# eilzugwagen.net
KiCad netlist of a schematic drawn in EAGLE
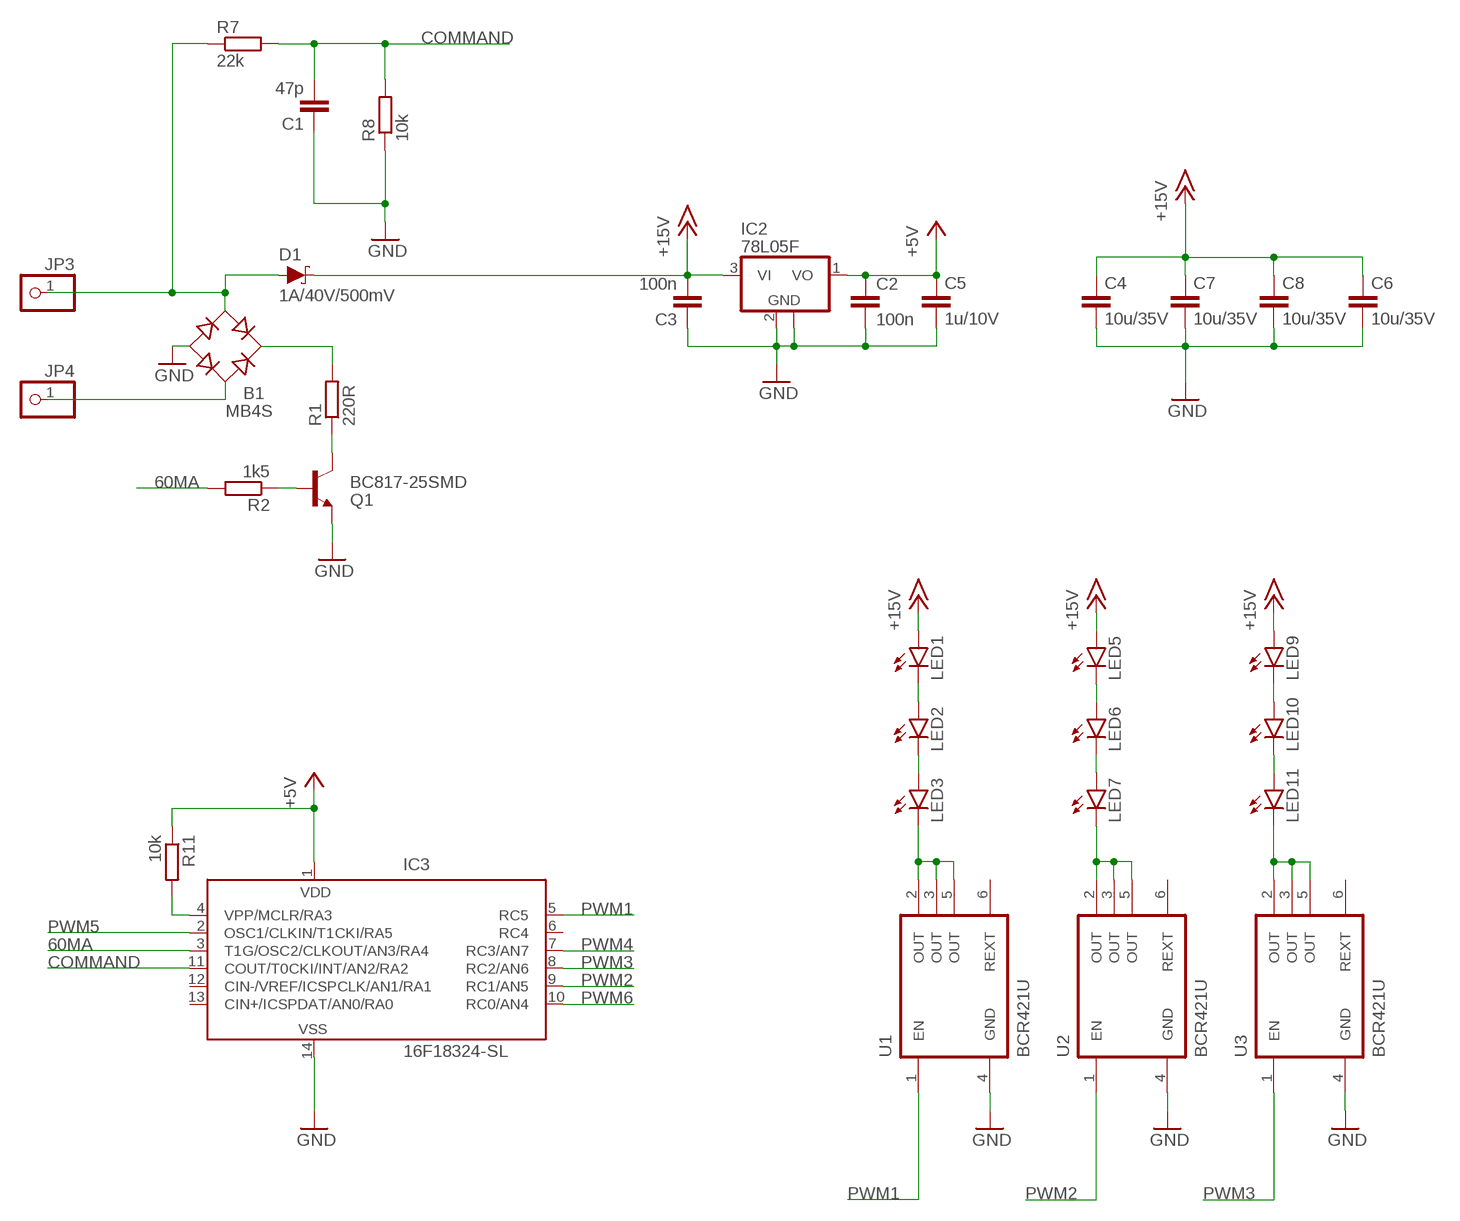
[diagram p0: schematic, sheet 1]

(export (version "E")
  (design (tool "Eeschema 10.0.6"))
  (components
    (comp (ref "B1")
      (value "MB4S")
      (footprint "eagle-import:SOIC-4")
      (libsource (lib "eagle-import") (part "MBS4"))
    )
    (comp (ref "C1")
      (value "47p")
      (footprint "eagle-import:C0805")
      (libsource (lib "eagle-import") (part "C-EUC0805"))
    )
    (comp (ref "C2")
      (value "100n")
      (footprint "eagle-import:C3216")
      (libsource (lib "eagle-import") (part "C-EUC3216"))
    )
    (comp (ref "C3")
      (value "100n")
      (footprint "eagle-import:C3216")
      (libsource (lib "eagle-import") (part "C-EUC3216"))
    )
    (comp (ref "C4")
      (value "10u/35V")
      (footprint "eagle-import:C3216")
      (libsource (lib "eagle-import") (part "C-EUC3216"))
    )
    (comp (ref "C5")
      (value "1u/10V")
      (footprint "eagle-import:C3216")
      (libsource (lib "eagle-import") (part "C-EUC3216"))
    )
    (comp (ref "C6")
      (value "10u/35V")
      (footprint "eagle-import:C3216")
      (libsource (lib "eagle-import") (part "C-EUC3216"))
    )
    (comp (ref "C7")
      (value "10u/35V")
      (footprint "eagle-import:C3216")
      (libsource (lib "eagle-import") (part "C-EUC3216"))
    )
    (comp (ref "C8")
      (value "10u/35V")
      (footprint "eagle-import:C3216")
      (libsource (lib "eagle-import") (part "C-EUC3216"))
    )
    (comp (ref "D1")
      (value "1A/40V/500mV")
      (footprint "eagle-import:SMA-DIODE")
      (libsource (lib "eagle-import") (part "DIODE-SCHOTTKY-SS14"))
    )
    (comp (ref "IC2")
      (value "78L05F")
      (footprint "eagle-import:SOT89")
      (libsource (lib "eagle-import") (part "78LF05"))
    )
    (comp (ref "IC3")
      (value "16F18324-SL")
      (footprint "eagle-import:SO-14")
      (fields (field (name "MF") "MICROCHIP") (field (name "MPN") "PIC16F676-I/SL"))
      (libsource (lib "eagle-import") (part "PIC16F676SL"))
    )
    (comp (ref "JP3")
      (value "PINHD-1X1")
      (footprint "eagle-import:1X01")
      (libsource (lib "eagle-import") (part "PINHD-1X1"))
    )
    (comp (ref "JP4")
      (value "PINHD-1X1")
      (footprint "eagle-import:1X01")
      (libsource (lib "eagle-import") (part "PINHD-1X1"))
    )
    (comp (ref "LED1")
      (value "LEDKA-3528ASYC")
      (footprint "eagle-import:KA-3528ASYC")
      (libsource (lib "eagle-import") (part "LEDKA-3528ASYC"))
    )
    (comp (ref "LED2")
      (value "LEDKA-3528ASYC")
      (footprint "eagle-import:KA-3528ASYC")
      (libsource (lib "eagle-import") (part "LEDKA-3528ASYC"))
    )
    (comp (ref "LED3")
      (value "LEDKA-3528ASYC")
      (footprint "eagle-import:KA-3528ASYC")
      (libsource (lib "eagle-import") (part "LEDKA-3528ASYC"))
    )
    (comp (ref "LED5")
      (value "LEDKA-3528ASYC")
      (footprint "eagle-import:KA-3528ASYC")
      (libsource (lib "eagle-import") (part "LEDKA-3528ASYC"))
    )
    (comp (ref "LED6")
      (value "LEDKA-3528ASYC")
      (footprint "eagle-import:KA-3528ASYC")
      (libsource (lib "eagle-import") (part "LEDKA-3528ASYC"))
    )
    (comp (ref "LED7")
      (value "LEDKA-3528ASYC")
      (footprint "eagle-import:KA-3528ASYC")
      (libsource (lib "eagle-import") (part "LEDKA-3528ASYC"))
    )
    (comp (ref "LED9")
      (value "LEDKA-3528ASYC")
      (footprint "eagle-import:KA-3528ASYC")
      (libsource (lib "eagle-import") (part "LEDKA-3528ASYC"))
    )
    (comp (ref "LED10")
      (value "LEDKA-3528ASYC")
      (footprint "eagle-import:KA-3528ASYC")
      (libsource (lib "eagle-import") (part "LEDKA-3528ASYC"))
    )
    (comp (ref "LED11")
      (value "LEDKA-3528ASYC")
      (footprint "eagle-import:KA-3528ASYC")
      (libsource (lib "eagle-import") (part "LEDKA-3528ASYC"))
    )
    (comp (ref "Q1")
      (value "BC817-25SMD")
      (footprint "eagle-import:SOT23-BEC")
      (libsource (lib "eagle-import") (part "BC817SMD-25"))
    )
    (comp (ref "R1")
      (value "220R")
      (footprint "eagle-import:R1206")
      (libsource (lib "eagle-import") (part "R-EU_R1206"))
    )
    (comp (ref "R2")
      (value "1k5")
      (footprint "eagle-import:R1206")
      (libsource (lib "eagle-import") (part "R-EU_R1206"))
    )
    (comp (ref "R7")
      (value "22k")
      (footprint "eagle-import:R1206")
      (libsource (lib "eagle-import") (part "R-EU_R1206"))
    )
    (comp (ref "R8")
      (value "10k")
      (footprint "eagle-import:R1206")
      (libsource (lib "eagle-import") (part "R-EU_R1206"))
    )
    (comp (ref "R11")
      (value "10k")
      (footprint "eagle-import:R1206")
      (libsource (lib "eagle-import") (part "R-EU_R1206"))
    )
    (comp (ref "U1")
      (value "BCR421U")
      (footprint "eagle-import:SC74-6")
      (fields (field (name "MF") "Infineon"))
      (libsource (lib "eagle-import") (part "BCR421U"))
    )
    (comp (ref "U2")
      (value "BCR421U")
      (footprint "eagle-import:SC74-6")
      (fields (field (name "MF") "Infineon"))
      (libsource (lib "eagle-import") (part "BCR421U"))
    )
    (comp (ref "U3")
      (value "BCR421U")
      (footprint "eagle-import:SC74-6")
      (fields (field (name "MF") "Infineon"))
      (libsource (lib "eagle-import") (part "BCR421U"))
    )
  )
  (nets
    (net (code "1") (name "+5V") (class "Default")
      (node (ref "C2") (pin "1") (pinfunction "1_1") (pintype "passive"))
      (node (ref "C5") (pin "1") (pinfunction "1_1") (pintype "passive"))
      (node (ref "IC2") (pin "1") (pinfunction "VO_1") (pintype "passive"))
      (node (ref "IC3") (pin "1") (pinfunction "VDD_1") (pintype "power_in"))
      (node (ref "R11") (pin "1") (pinfunction "1_1") (pintype "passive"))
    )
    (net (code "2") (name "+15V") (class "Default")
      (node (ref "C3") (pin "2") (pinfunction "2_2") (pintype "passive"))
      (node (ref "C4") (pin "1") (pinfunction "1_1") (pintype "passive"))
      (node (ref "C6") (pin "1") (pinfunction "1_1") (pintype "passive"))
      (node (ref "C7") (pin "1") (pinfunction "1_1") (pintype "passive"))
      (node (ref "C8") (pin "1") (pinfunction "1_1") (pintype "passive"))
      (node (ref "D1") (pin "C") (pinfunction "C_C") (pintype "passive"))
      (node (ref "IC2") (pin "3") (pinfunction "VI_3") (pintype "input"))
      (node (ref "LED1") (pin "A") (pinfunction "A_A") (pintype "passive"))
      (node (ref "LED5") (pin "A") (pinfunction "A_A") (pintype "passive"))
      (node (ref "LED9") (pin "A") (pinfunction "A_A") (pintype "passive"))
    )
    (net (code "3") (name "/60MA") (class "Default")
      (node (ref "IC3") (pin "3") (pinfunction "T1G/OSC2/CLKOUT/AN3/RA4_3") (pintype "bidirectional"))
      (node (ref "R2") (pin "2") (pinfunction "2_2") (pintype "passive"))
    )
    (net (code "4") (name "/COMMAND") (class "Default")
      (node (ref "C1") (pin "2") (pinfunction "2_2") (pintype "passive"))
      (node (ref "IC3") (pin "11") (pinfunction "COUT/T0CKI/INT/AN2/RA2_11") (pintype "bidirectional"))
      (node (ref "R7") (pin "2") (pinfunction "2_2") (pintype "passive"))
      (node (ref "R8") (pin "2") (pinfunction "2_2") (pintype "passive"))
    )
    (net (code "5") (name "/PWM1") (class "Default")
      (node (ref "IC3") (pin "5") (pinfunction "RC5_5") (pintype "bidirectional"))
      (node (ref "U1") (pin "1") (pinfunction "EN_1") (pintype "input"))
    )
    (net (code "6") (name "/PWM2") (class "Default")
      (node (ref "IC3") (pin "9") (pinfunction "RC1/AN5_9") (pintype "bidirectional"))
      (node (ref "U2") (pin "1") (pinfunction "EN_1") (pintype "input"))
    )
    (net (code "7") (name "/PWM3") (class "Default")
      (node (ref "IC3") (pin "8") (pinfunction "RC2/AN6_8") (pintype "bidirectional"))
      (node (ref "U3") (pin "1") (pinfunction "EN_1") (pintype "input"))
    )
    (net (code "8") (name "/PWM4") (class "Default")
      (node (ref "IC3") (pin "7") (pinfunction "RC3/AN7_7") (pintype "bidirectional"))
    )
    (net (code "9") (name "/PWM5") (class "Default")
      (node (ref "IC3") (pin "2") (pinfunction "OSC1/CLKIN/T1CKI/RA5_2") (pintype "bidirectional"))
    )
    (net (code "10") (name "/PWM6") (class "Default")
      (node (ref "IC3") (pin "10") (pinfunction "RC0/AN4_10") (pintype "bidirectional"))
    )
    (net (code "11") (name "GND") (class "Default")
      (node (ref "B1") (pin "-") (pinfunction "-_-") (pintype "passive"))
      (node (ref "C1") (pin "1") (pinfunction "1_1") (pintype "passive"))
      (node (ref "C2") (pin "2") (pinfunction "2_2") (pintype "passive"))
      (node (ref "C3") (pin "1") (pinfunction "1_1") (pintype "passive"))
      (node (ref "C4") (pin "2") (pinfunction "2_2") (pintype "passive"))
      (node (ref "C5") (pin "2") (pinfunction "2_2") (pintype "passive"))
      (node (ref "C6") (pin "2") (pinfunction "2_2") (pintype "passive"))
      (node (ref "C7") (pin "2") (pinfunction "2_2") (pintype "passive"))
      (node (ref "C8") (pin "2") (pinfunction "2_2") (pintype "passive"))
      (node (ref "IC2") (pin "2") (pinfunction "GND_2") (pintype "passive"))
      (node (ref "IC2") (pin "2@1") (pinfunction "GND_2@1") (pintype "passive"))
      (node (ref "IC3") (pin "14") (pinfunction "VSS_14") (pintype "power_in"))
      (node (ref "Q1") (pin "E") (pinfunction "E_E") (pintype "passive"))
      (node (ref "R8") (pin "1") (pinfunction "1_1") (pintype "passive"))
      (node (ref "U1") (pin "4") (pinfunction "GND_4") (pintype "input"))
      (node (ref "U2") (pin "4") (pinfunction "GND_4") (pintype "input"))
      (node (ref "U3") (pin "4") (pinfunction "GND_4") (pintype "input"))
    )
    (net (code "12") (name "Net-(B1-AC1)") (class "Default")
      (node (ref "B1") (pin "~1") (pinfunction "AC1_~1") (pintype "passive"))
      (node (ref "D1") (pin "A") (pinfunction "A_A") (pintype "passive"))
      (node (ref "JP3") (pin "1") (pinfunction "1_1") (pintype "passive"))
      (node (ref "R7") (pin "1") (pinfunction "1_1") (pintype "passive"))
    )
    (net (code "13") (name "Net-(B1-AC2)") (class "Default")
      (node (ref "B1") (pin "~2") (pinfunction "AC2_~2") (pintype "passive"))
      (node (ref "JP4") (pin "1") (pinfunction "1_1") (pintype "passive"))
    )
    (net (code "14") (name "Net-(B1-Pad+)") (class "Default")
      (node (ref "B1") (pin "+") (pinfunction "+_+") (pintype "passive"))
      (node (ref "R1") (pin "2") (pinfunction "2_2") (pintype "passive"))
    )
    (net (code "15") (name "Net-(IC3-VPP{slash}MCLR{slash}RA3)") (class "Default")
      (node (ref "IC3") (pin "4") (pinfunction "VPP/MCLR/RA3_4") (pintype "input"))
      (node (ref "R11") (pin "2") (pinfunction "2_2") (pintype "passive"))
    )
    (net (code "16") (name "Net-(LED1-PadC)") (class "Default")
      (node (ref "LED1") (pin "C") (pinfunction "C_C") (pintype "passive"))
      (node (ref "LED2") (pin "A") (pinfunction "A_A") (pintype "passive"))
    )
    (net (code "17") (name "Net-(LED2-PadC)") (class "Default")
      (node (ref "LED2") (pin "C") (pinfunction "C_C") (pintype "passive"))
      (node (ref "LED3") (pin "A") (pinfunction "A_A") (pintype "passive"))
    )
    (net (code "18") (name "Net-(LED3-PadC)") (class "Default")
      (node (ref "LED3") (pin "C") (pinfunction "C_C") (pintype "passive"))
      (node (ref "U1") (pin "2") (pinfunction "OUT_2") (pintype "open_collector"))
      (node (ref "U1") (pin "3") (pinfunction "OUT_3") (pintype "open_collector"))
      (node (ref "U1") (pin "5") (pinfunction "OUT_5") (pintype "open_collector"))
    )
    (net (code "19") (name "Net-(LED5-PadC)") (class "Default")
      (node (ref "LED5") (pin "C") (pinfunction "C_C") (pintype "passive"))
      (node (ref "LED6") (pin "A") (pinfunction "A_A") (pintype "passive"))
    )
    (net (code "20") (name "Net-(LED6-PadC)") (class "Default")
      (node (ref "LED6") (pin "C") (pinfunction "C_C") (pintype "passive"))
      (node (ref "LED7") (pin "A") (pinfunction "A_A") (pintype "passive"))
    )
    (net (code "21") (name "Net-(LED7-PadC)") (class "Default")
      (node (ref "LED7") (pin "C") (pinfunction "C_C") (pintype "passive"))
      (node (ref "U2") (pin "2") (pinfunction "OUT_2") (pintype "open_collector"))
      (node (ref "U2") (pin "3") (pinfunction "OUT_3") (pintype "open_collector"))
      (node (ref "U2") (pin "5") (pinfunction "OUT_5") (pintype "open_collector"))
    )
    (net (code "22") (name "Net-(LED10-PadA)") (class "Default")
      (node (ref "LED10") (pin "A") (pinfunction "A_A") (pintype "passive"))
      (node (ref "LED9") (pin "C") (pinfunction "C_C") (pintype "passive"))
    )
    (net (code "23") (name "Net-(LED10-PadC)") (class "Default")
      (node (ref "LED10") (pin "C") (pinfunction "C_C") (pintype "passive"))
      (node (ref "LED11") (pin "A") (pinfunction "A_A") (pintype "passive"))
    )
    (net (code "24") (name "Net-(LED11-PadC)") (class "Default")
      (node (ref "LED11") (pin "C") (pinfunction "C_C") (pintype "passive"))
      (node (ref "U3") (pin "2") (pinfunction "OUT_2") (pintype "open_collector"))
      (node (ref "U3") (pin "3") (pinfunction "OUT_3") (pintype "open_collector"))
      (node (ref "U3") (pin "5") (pinfunction "OUT_5") (pintype "open_collector"))
    )
    (net (code "25") (name "Net-(Q1-PadB)") (class "Default")
      (node (ref "Q1") (pin "B") (pinfunction "B_B") (pintype "passive"))
      (node (ref "R2") (pin "1") (pinfunction "1_1") (pintype "passive"))
    )
    (net (code "26") (name "Net-(Q1-PadC)") (class "Default")
      (node (ref "Q1") (pin "C") (pinfunction "C_C") (pintype "passive"))
      (node (ref "R1") (pin "1") (pinfunction "1_1") (pintype "passive"))
    )
    (net (code "27") (name "unconnected-(IC3-CIN+{slash}ICSPDAT{slash}AN0{slash}RA0-Pad13)") (class "Default")
      (node (ref "IC3") (pin "13") (pinfunction "CIN+/ICSPDAT/AN0/RA0_13") (pintype "bidirectional"))
    )
    (net (code "28") (name "unconnected-(IC3-CIN-{slash}VREF{slash}ICSPCLK{slash}AN1{slash}RA1-Pad12)") (class "Default")
      (node (ref "IC3") (pin "12") (pinfunction "CIN-/VREF/ICSPCLK/AN1/RA1_12") (pintype "bidirectional"))
    )
    (net (code "29") (name "unconnected-(IC3-RC4-Pad6)") (class "Default")
      (node (ref "IC3") (pin "6") (pinfunction "RC4_6") (pintype "bidirectional"))
    )
    (net (code "30") (name "unconnected-(U1-REXT-Pad6)") (class "Default")
      (node (ref "U1") (pin "6") (pinfunction "REXT_6") (pintype "bidirectional"))
    )
    (net (code "31") (name "unconnected-(U2-REXT-Pad6)") (class "Default")
      (node (ref "U2") (pin "6") (pinfunction "REXT_6") (pintype "bidirectional"))
    )
    (net (code "32") (name "unconnected-(U3-REXT-Pad6)") (class "Default")
      (node (ref "U3") (pin "6") (pinfunction "REXT_6") (pintype "bidirectional"))
    )
  )
)
